# POWER.net
KiCad netlist of a schematic drawn in Altium Designer
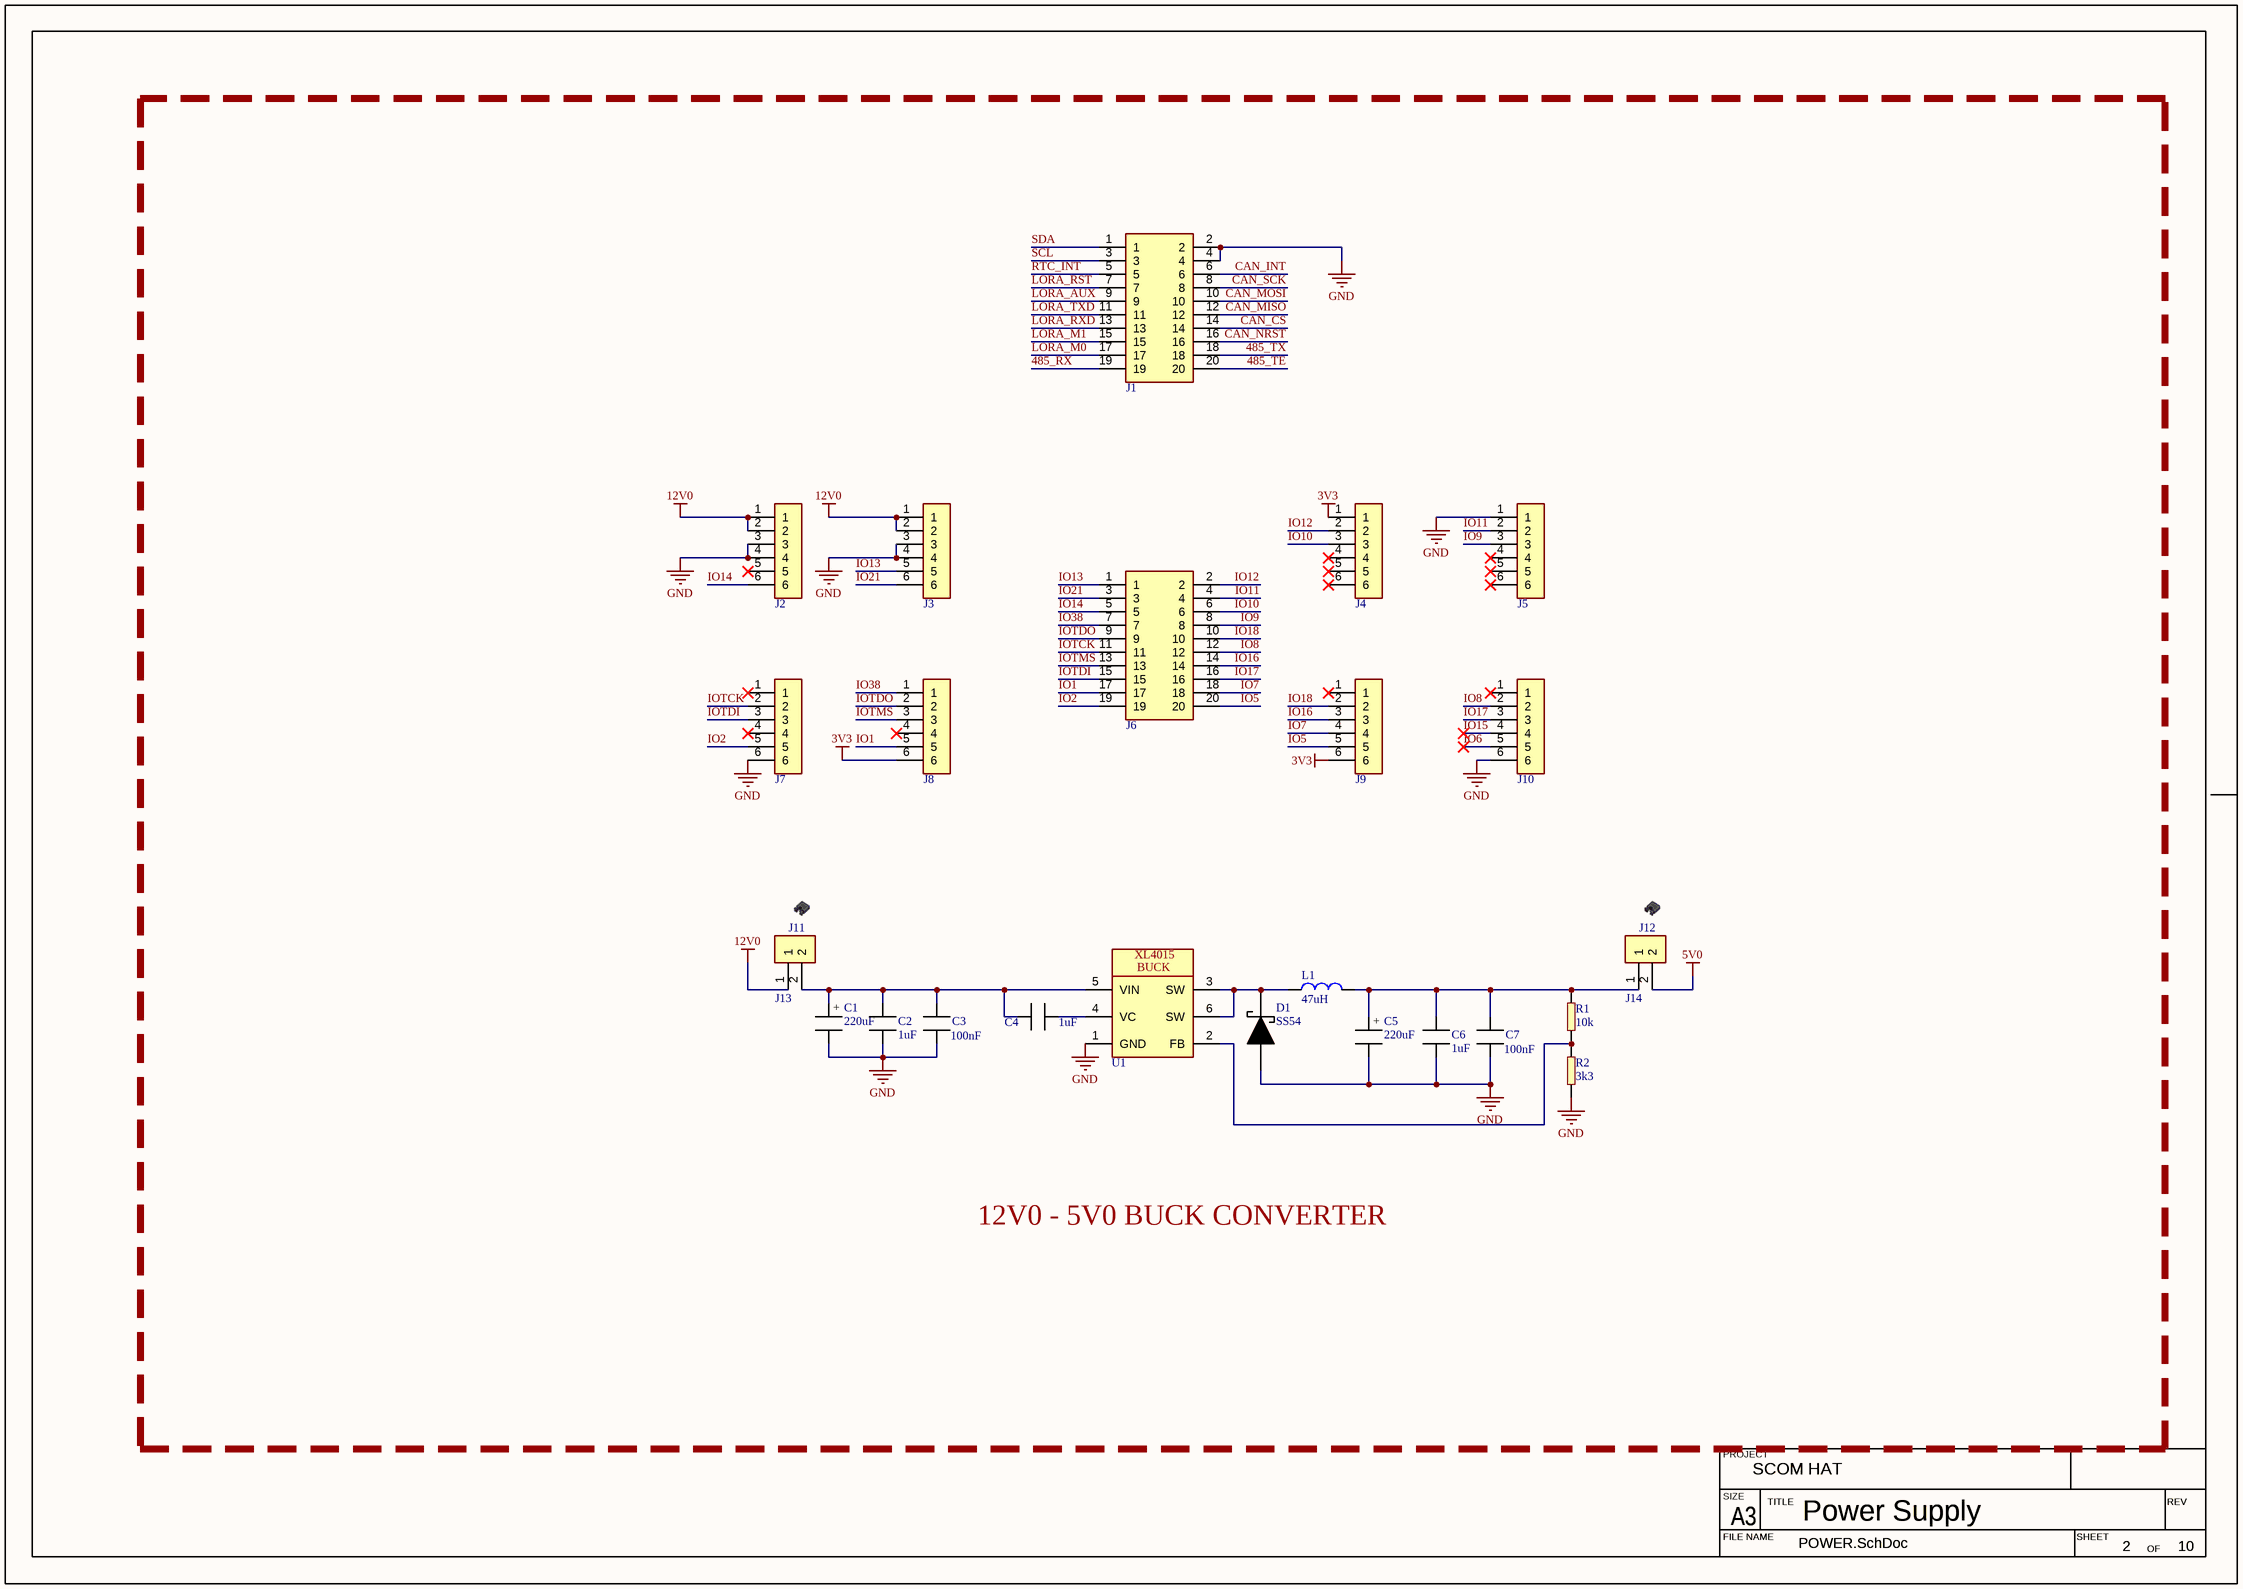
[diagram p0: POWER.SchDoc]

(export (version "E")
  (design (tool "Eeschema 10.0.6"))
  (components
    (comp (ref "C1")
      (value "220uF")
      (footprint "CAP_D10_H16_P5 - Flat")
      (description "Electrolytic Capacitor Through Hole D10 P5.0")
      (fields (field (name "Comment") "ERP_102-2"))
      (libsource (lib "ElectrolyticCapacitor") (part "CAP_D10_H16_P5"))
    )
    (comp (ref "C2")
      (value "1uF")
      (footprint "CAPC2012X13L")
      (description "Chip Capacitor, 2-Leads, Body 2.00x1.25mm, IPC High Density")
      (fields (field (name "Comment") "MLCC_0805"))
      (libsource (lib "Capacitor") (part "MLCC_0805"))
    )
    (comp (ref "C3")
      (value "100nF")
      (footprint "CAPC2012X13L")
      (description "Chip Capacitor, 2-Leads, Body 2.00x1.25mm, IPC High Density")
      (fields (field (name "Comment") "MLCC_0805"))
      (libsource (lib "Capacitor") (part "MLCC_0805"))
    )
    (comp (ref "C4")
      (value "1uF")
      (footprint "CAPC2012X13L")
      (description "Chip Capacitor, 2-Leads, Body 2.00x1.25mm, IPC High Density")
      (fields (field (name "Comment") "MLCC_0805"))
      (libsource (lib "Capacitor") (part "MLCC_0805"))
    )
    (comp (ref "C5")
      (value "220uF")
      (footprint "CAP_D10_H16_P5 - Flat")
      (description "Electrolytic Capacitor Through Hole D10 P5.0")
      (fields (field (name "Comment") "ERP_102-2"))
      (libsource (lib "ElectrolyticCapacitor") (part "CAP_D10_H16_P5"))
    )
    (comp (ref "C6")
      (value "1uF")
      (footprint "CAPC2012X13L")
      (description "Chip Capacitor, 2-Leads, Body 2.00x1.25mm, IPC High Density")
      (fields (field (name "Comment") "MLCC_0805"))
      (libsource (lib "Capacitor") (part "MLCC_0805"))
    )
    (comp (ref "C7")
      (value "100nF")
      (footprint "CAPC2012X13L")
      (description "Chip Capacitor, 2-Leads, Body 2.00x1.25mm, IPC High Density")
      (fields (field (name "Comment") "MLCC_0805"))
      (libsource (lib "Capacitor") (part "MLCC_0805"))
    )
    (comp (ref "D1")
      (value "SS54")
      (footprint "DIOM6959X26L")
      (fields (field (name "Comment") "ERP_104-3"))
      (libsource (lib "Schottky") (part "SS54"))
    )
    (comp (ref "J1")
      (value "20PX2R_M")
      (footprint "20PX2R_Male_THT_Shrouded")
      (description "Connector Header Surface Mount 20 position 0.100\" (2.54mm)")
      (libsource (lib "PinHeader") (part "20PX2R_M"))
    )
    (comp (ref "J2")
      (value "6PX1R_M")
      (footprint "6PX1R_M_STK20")
      (description "6PX1R Male Header")
      (libsource (lib "PinHeader") (part "6PX1R_M"))
    )
    (comp (ref "J3")
      (value "6PX1R_M")
      (footprint "6PX1R_M_STK20")
      (description "6PX1R Male Header")
      (libsource (lib "PinHeader") (part "6PX1R_M"))
    )
    (comp (ref "J4")
      (value "6PX1R_M")
      (footprint "6PX1R_M_STK20")
      (description "6PX1R Male Header")
      (libsource (lib "PinHeader") (part "6PX1R_M"))
    )
    (comp (ref "J5")
      (value "6PX1R_M")
      (footprint "6PX1R_M_STK20")
      (description "6PX1R Male Header")
      (libsource (lib "PinHeader") (part "6PX1R_M"))
    )
    (comp (ref "J6")
      (value "20PX2R_M")
      (footprint "20PX2R_Male_THT_Shrouded")
      (description "Connector Header Surface Mount 20 position 0.100\" (2.54mm)")
      (libsource (lib "PinHeader") (part "20PX2R_M"))
    )
    (comp (ref "J7")
      (value "6PX1R_M")
      (footprint "6PX1R_M_STK20")
      (description "6PX1R Male Header")
      (libsource (lib "PinHeader") (part "6PX1R_M"))
    )
    (comp (ref "J8")
      (value "6PX1R_M")
      (footprint "6PX1R_M_STK20")
      (description "6PX1R Male Header")
      (libsource (lib "PinHeader") (part "6PX1R_M"))
    )
    (comp (ref "J9")
      (value "6PX1R_M")
      (footprint "6PX1R_M_STK20")
      (description "6PX1R Male Header")
      (libsource (lib "PinHeader") (part "6PX1R_M"))
    )
    (comp (ref "J10")
      (value "6PX1R_M")
      (footprint "6PX1R_M_STK20")
      (description "6PX1R Male Header")
      (libsource (lib "PinHeader") (part "6PX1R_M"))
    )
    (comp (ref "J11")
      (value "Jumper Cap")
      (description "2 Pin Jumper Cap P2.54")
      (libsource (lib "Jumper") (part "Jumper Cap"))
    )
    (comp (ref "J12")
      (value "Jumper Cap")
      (description "2 Pin Jumper Cap P2.54")
      (libsource (lib "Jumper") (part "Jumper Cap"))
    )
    (comp (ref "J13") (value "2PX1R") (footprint "2PX1R") (libsource (lib "PinHeader") (part "2PX1R")))
    (comp (ref "J14") (value "2PX1R") (footprint "2PX1R") (libsource (lib "PinHeader") (part "2PX1R")))
    (comp (ref "L1")
      (value "47uH")
      (footprint "IND_1212")
      (description "IND_1212")
      (fields (field (name "Comment") "ERP_103-3"))
      (libsource (lib "Inductor") (part "IND_1212"))
    )
    (comp (ref "R1")
      (value "10k")
      (footprint "RES_0603")
      (description "RES_0603")
      (fields (field (name "Comment") "ERP_101-1"))
      (libsource (lib "Resistor") (part "RES_0603"))
    )
    (comp (ref "R2")
      (value "3k3")
      (footprint "RES_0603")
      (description "RES_0603")
      (fields (field (name "Comment") "ERP_101-1"))
      (libsource (lib "Resistor") (part "RES_0603"))
    )
    (comp (ref "U1")
      (value "XL4015")
      (footprint "XL4015")
      (description "5A 180KHz 36V Buck DC to DC Converter")
      (libsource (lib "DCDC_Switcher") (part "XL4015"))
    )
  )
  (nets
    (net (code "1") (name "/485_RX") (class "Default")
      (node (ref "J1") (pin "19") (pinfunction "19_19") (pintype "passive"))
    )
    (net (code "2") (name "/485_TE") (class "Default")
      (node (ref "J1") (pin "20") (pinfunction "20_20") (pintype "passive"))
    )
    (net (code "3") (name "/485_TX") (class "Default")
      (node (ref "J1") (pin "18") (pinfunction "18_18") (pintype "passive"))
    )
    (net (code "4") (name "/CAN_CS") (class "Default")
      (node (ref "J1") (pin "14") (pinfunction "14_14") (pintype "passive"))
    )
    (net (code "5") (name "/CAN_INT") (class "Default")
      (node (ref "J1") (pin "6") (pinfunction "6_6") (pintype "passive"))
    )
    (net (code "6") (name "/CAN_MISO") (class "Default")
      (node (ref "J1") (pin "12") (pinfunction "12_12") (pintype "passive"))
    )
    (net (code "7") (name "/CAN_MOSI") (class "Default")
      (node (ref "J1") (pin "10") (pinfunction "10_10") (pintype "passive"))
    )
    (net (code "8") (name "/CAN_NRST") (class "Default")
      (node (ref "J1") (pin "16") (pinfunction "16_16") (pintype "passive"))
    )
    (net (code "9") (name "/CAN_SCK") (class "Default")
      (node (ref "J1") (pin "8") (pinfunction "8_8") (pintype "passive"))
    )
    (net (code "10") (name "/IO1") (class "Default")
      (node (ref "J6") (pin "17") (pinfunction "17_17") (pintype "passive"))
      (node (ref "J8") (pin "5") (pinfunction "5_5") (pintype "passive"))
    )
    (net (code "11") (name "/IO2") (class "Default")
      (node (ref "J6") (pin "19") (pinfunction "19_19") (pintype "passive"))
      (node (ref "J7") (pin "5") (pinfunction "5_5") (pintype "passive"))
    )
    (net (code "12") (name "/IO5") (class "Default")
      (node (ref "J6") (pin "20") (pinfunction "20_20") (pintype "passive"))
      (node (ref "J9") (pin "5") (pinfunction "5_5") (pintype "passive"))
    )
    (net (code "13") (name "/IO6") (class "Default")
      (node (ref "J10") (pin "5") (pinfunction "5_5") (pintype "passive+no_connect"))
    )
    (net (code "14") (name "/IO7") (class "Default")
      (node (ref "J6") (pin "18") (pinfunction "18_18") (pintype "passive"))
      (node (ref "J9") (pin "4") (pinfunction "4_4") (pintype "passive"))
    )
    (net (code "15") (name "/IO8") (class "Default")
      (node (ref "J10") (pin "2") (pinfunction "2_2") (pintype "passive"))
      (node (ref "J6") (pin "12") (pinfunction "12_12") (pintype "passive"))
    )
    (net (code "16") (name "/IO9") (class "Default")
      (node (ref "J5") (pin "3") (pinfunction "3_3") (pintype "passive"))
      (node (ref "J6") (pin "8") (pinfunction "8_8") (pintype "passive"))
    )
    (net (code "17") (name "/IO10") (class "Default")
      (node (ref "J4") (pin "3") (pinfunction "3_3") (pintype "passive"))
      (node (ref "J6") (pin "6") (pinfunction "6_6") (pintype "passive"))
    )
    (net (code "18") (name "/IO11") (class "Default")
      (node (ref "J5") (pin "2") (pinfunction "2_2") (pintype "passive"))
      (node (ref "J6") (pin "4") (pinfunction "4_4") (pintype "passive"))
    )
    (net (code "19") (name "/IO12") (class "Default")
      (node (ref "J4") (pin "2") (pinfunction "2_2") (pintype "passive"))
      (node (ref "J6") (pin "2") (pinfunction "2_2") (pintype "passive"))
    )
    (net (code "20") (name "/IO13") (class "Default")
      (node (ref "J3") (pin "5") (pinfunction "5_5") (pintype "passive"))
      (node (ref "J6") (pin "1") (pinfunction "1_1") (pintype "passive"))
    )
    (net (code "21") (name "/IO14") (class "Default")
      (node (ref "J2") (pin "6") (pinfunction "6_6") (pintype "passive"))
      (node (ref "J6") (pin "5") (pinfunction "5_5") (pintype "passive"))
    )
    (net (code "22") (name "/IO15") (class "Default")
      (node (ref "J10") (pin "4") (pinfunction "4_4") (pintype "passive+no_connect"))
    )
    (net (code "23") (name "/IO16") (class "Default")
      (node (ref "J6") (pin "14") (pinfunction "14_14") (pintype "passive"))
      (node (ref "J9") (pin "3") (pinfunction "3_3") (pintype "passive"))
    )
    (net (code "24") (name "/IO17") (class "Default")
      (node (ref "J10") (pin "3") (pinfunction "3_3") (pintype "passive"))
      (node (ref "J6") (pin "16") (pinfunction "16_16") (pintype "passive"))
    )
    (net (code "25") (name "/IO18") (class "Default")
      (node (ref "J6") (pin "10") (pinfunction "10_10") (pintype "passive"))
      (node (ref "J9") (pin "2") (pinfunction "2_2") (pintype "passive"))
    )
    (net (code "26") (name "/IO21") (class "Default")
      (node (ref "J3") (pin "6") (pinfunction "6_6") (pintype "passive"))
      (node (ref "J6") (pin "3") (pinfunction "3_3") (pintype "passive"))
    )
    (net (code "27") (name "/IO38") (class "Default")
      (node (ref "J6") (pin "7") (pinfunction "7_7") (pintype "passive"))
      (node (ref "J8") (pin "1") (pinfunction "1_1") (pintype "passive"))
    )
    (net (code "28") (name "/IOTCK") (class "Default")
      (node (ref "J6") (pin "11") (pinfunction "11_11") (pintype "passive"))
      (node (ref "J7") (pin "2") (pinfunction "2_2") (pintype "passive"))
    )
    (net (code "29") (name "/IOTDI") (class "Default")
      (node (ref "J6") (pin "15") (pinfunction "15_15") (pintype "passive"))
      (node (ref "J7") (pin "3") (pinfunction "3_3") (pintype "passive"))
    )
    (net (code "30") (name "/IOTDO") (class "Default")
      (node (ref "J6") (pin "9") (pinfunction "9_9") (pintype "passive"))
      (node (ref "J8") (pin "2") (pinfunction "2_2") (pintype "passive"))
    )
    (net (code "31") (name "/IOTMS") (class "Default")
      (node (ref "J6") (pin "13") (pinfunction "13_13") (pintype "passive"))
      (node (ref "J8") (pin "3") (pinfunction "3_3") (pintype "passive"))
    )
    (net (code "32") (name "/LORA_AUX") (class "Default")
      (node (ref "J1") (pin "9") (pinfunction "9_9") (pintype "passive"))
    )
    (net (code "33") (name "/LORA_M0") (class "Default")
      (node (ref "J1") (pin "17") (pinfunction "17_17") (pintype "passive"))
    )
    (net (code "34") (name "/LORA_M1") (class "Default")
      (node (ref "J1") (pin "15") (pinfunction "15_15") (pintype "passive"))
    )
    (net (code "35") (name "/LORA_RST") (class "Default")
      (node (ref "J1") (pin "7") (pinfunction "7_7") (pintype "passive"))
    )
    (net (code "36") (name "/LORA_RXD") (class "Default")
      (node (ref "J1") (pin "13") (pinfunction "13_13") (pintype "passive"))
    )
    (net (code "37") (name "/LORA_TXD") (class "Default")
      (node (ref "J1") (pin "11") (pinfunction "11_11") (pintype "passive"))
    )
    (net (code "38") (name "/RTC_INT") (class "Default")
      (node (ref "J1") (pin "5") (pinfunction "5_5") (pintype "passive"))
    )
    (net (code "39") (name "/SCL") (class "Default")
      (node (ref "J1") (pin "3") (pinfunction "3_3") (pintype "passive"))
    )
    (net (code "40") (name "/SDA") (class "Default")
      (node (ref "J1") (pin "1") (pinfunction "1_1") (pintype "passive"))
    )
    (net (code "41") (name "3V3") (class "Default")
      (node (ref "J4") (pin "1") (pinfunction "1_1") (pintype "passive"))
      (node (ref "J8") (pin "6") (pinfunction "6_6") (pintype "passive"))
      (node (ref "J9") (pin "6") (pinfunction "6_6") (pintype "passive"))
    )
    (net (code "42") (name "5V0") (class "Default")
      (node (ref "J14") (pin "2") (pinfunction "2_2") (pintype "passive"))
    )
    (net (code "43") (name "12V0") (class "Default")
      (node (ref "J13") (pin "1") (pinfunction "1_1") (pintype "passive"))
      (node (ref "J2") (pin "1") (pinfunction "1_1") (pintype "passive"))
      (node (ref "J2") (pin "2") (pinfunction "2_2") (pintype "passive"))
      (node (ref "J3") (pin "1") (pinfunction "1_1") (pintype "passive"))
      (node (ref "J3") (pin "2") (pinfunction "2_2") (pintype "passive"))
    )
    (net (code "44") (name "GND") (class "Default")
      (node (ref "C1") (pin "2") (pinfunction "2_2") (pintype "passive"))
      (node (ref "C2") (pin "2") (pinfunction "2_2") (pintype "passive"))
      (node (ref "C3") (pin "2") (pinfunction "2_2") (pintype "passive"))
      (node (ref "C5") (pin "2") (pinfunction "2_2") (pintype "passive"))
      (node (ref "C6") (pin "2") (pinfunction "2_2") (pintype "passive"))
      (node (ref "C7") (pin "2") (pinfunction "2_2") (pintype "passive"))
      (node (ref "D1") (pin "2") (pinfunction "A_2") (pintype "passive"))
      (node (ref "J1") (pin "2") (pinfunction "2_2") (pintype "passive"))
      (node (ref "J1") (pin "4") (pinfunction "4_4") (pintype "passive"))
      (node (ref "J10") (pin "6") (pinfunction "6_6") (pintype "passive"))
      (node (ref "J2") (pin "3") (pinfunction "3_3") (pintype "passive"))
      (node (ref "J2") (pin "4") (pinfunction "4_4") (pintype "passive"))
      (node (ref "J3") (pin "3") (pinfunction "3_3") (pintype "passive"))
      (node (ref "J3") (pin "4") (pinfunction "4_4") (pintype "passive"))
      (node (ref "J5") (pin "1") (pinfunction "1_1") (pintype "passive"))
      (node (ref "J7") (pin "6") (pinfunction "6_6") (pintype "passive"))
      (node (ref "R2") (pin "2") (pinfunction "2_2") (pintype "passive"))
      (node (ref "U1") (pin "1") (pinfunction "GND_1") (pintype "passive"))
    )
    (net (code "45") (name "Net-(C5-Pad1)") (class "Default")
      (node (ref "C5") (pin "1") (pinfunction "1_1") (pintype "passive"))
      (node (ref "C6") (pin "1") (pinfunction "1_1") (pintype "passive"))
      (node (ref "C7") (pin "1") (pinfunction "1_1") (pintype "passive"))
      (node (ref "J14") (pin "1") (pinfunction "1_1") (pintype "passive"))
      (node (ref "L1") (pin "2") (pinfunction "2_2") (pintype "passive"))
      (node (ref "R1") (pin "1") (pinfunction "1_1") (pintype "passive"))
    )
    (net (code "46") (name "Net-(D1-C)") (class "Default")
      (node (ref "D1") (pin "1") (pinfunction "C_1") (pintype "passive"))
      (node (ref "L1") (pin "1") (pinfunction "1_1") (pintype "passive"))
      (node (ref "U1") (pin "3") (pinfunction "SW_3") (pintype "passive"))
      (node (ref "U1") (pin "6") (pinfunction "SW_6") (pintype "passive"))
    )
    (net (code "47") (name "Net-(U1-FB)") (class "Default")
      (node (ref "R1") (pin "2") (pinfunction "2_2") (pintype "passive"))
      (node (ref "R2") (pin "1") (pinfunction "1_1") (pintype "passive"))
      (node (ref "U1") (pin "2") (pinfunction "FB_2") (pintype "passive"))
    )
    (net (code "48") (name "Net-(U1-VC)") (class "Default")
      (node (ref "C4") (pin "2") (pinfunction "2_2") (pintype "passive"))
      (node (ref "U1") (pin "4") (pinfunction "VC_4") (pintype "passive"))
    )
    (net (code "49") (name "Net-(U1-VIN)") (class "Default")
      (node (ref "C1") (pin "1") (pinfunction "1_1") (pintype "passive"))
      (node (ref "C2") (pin "1") (pinfunction "1_1") (pintype "passive"))
      (node (ref "C3") (pin "1") (pinfunction "1_1") (pintype "passive"))
      (node (ref "C4") (pin "1") (pinfunction "1_1") (pintype "passive"))
      (node (ref "J13") (pin "2") (pinfunction "2_2") (pintype "passive"))
      (node (ref "U1") (pin "5") (pinfunction "VIN_5") (pintype "passive"))
    )
    (net (code "50") (name "unconnected-(J2-Pad5)") (class "Default")
      (node (ref "J2") (pin "5") (pinfunction "5_5") (pintype "passive+no_connect"))
    )
    (net (code "51") (name "unconnected-(J4-Pad4)") (class "Default")
      (node (ref "J4") (pin "4") (pinfunction "4_4") (pintype "passive+no_connect"))
    )
    (net (code "52") (name "unconnected-(J4-Pad5)") (class "Default")
      (node (ref "J4") (pin "5") (pinfunction "5_5") (pintype "passive+no_connect"))
    )
    (net (code "53") (name "unconnected-(J4-Pad6)") (class "Default")
      (node (ref "J4") (pin "6") (pinfunction "6_6") (pintype "passive+no_connect"))
    )
    (net (code "54") (name "unconnected-(J5-Pad4)") (class "Default")
      (node (ref "J5") (pin "4") (pinfunction "4_4") (pintype "passive+no_connect"))
    )
    (net (code "55") (name "unconnected-(J5-Pad5)") (class "Default")
      (node (ref "J5") (pin "5") (pinfunction "5_5") (pintype "passive+no_connect"))
    )
    (net (code "56") (name "unconnected-(J5-Pad6)") (class "Default")
      (node (ref "J5") (pin "6") (pinfunction "6_6") (pintype "passive+no_connect"))
    )
    (net (code "57") (name "unconnected-(J7-Pad1)") (class "Default")
      (node (ref "J7") (pin "1") (pinfunction "1_1") (pintype "passive+no_connect"))
    )
    (net (code "58") (name "unconnected-(J7-Pad4)") (class "Default")
      (node (ref "J7") (pin "4") (pinfunction "4_4") (pintype "passive+no_connect"))
    )
    (net (code "59") (name "unconnected-(J8-Pad4)") (class "Default")
      (node (ref "J8") (pin "4") (pinfunction "4_4") (pintype "passive+no_connect"))
    )
    (net (code "60") (name "unconnected-(J9-Pad1)") (class "Default")
      (node (ref "J9") (pin "1") (pinfunction "1_1") (pintype "passive+no_connect"))
    )
    (net (code "61") (name "unconnected-(J10-Pad1)") (class "Default")
      (node (ref "J10") (pin "1") (pinfunction "1_1") (pintype "passive+no_connect"))
    )
  )
)
